# Adafruit_ICM20948.net
KiCad netlist of a schematic drawn in EAGLE
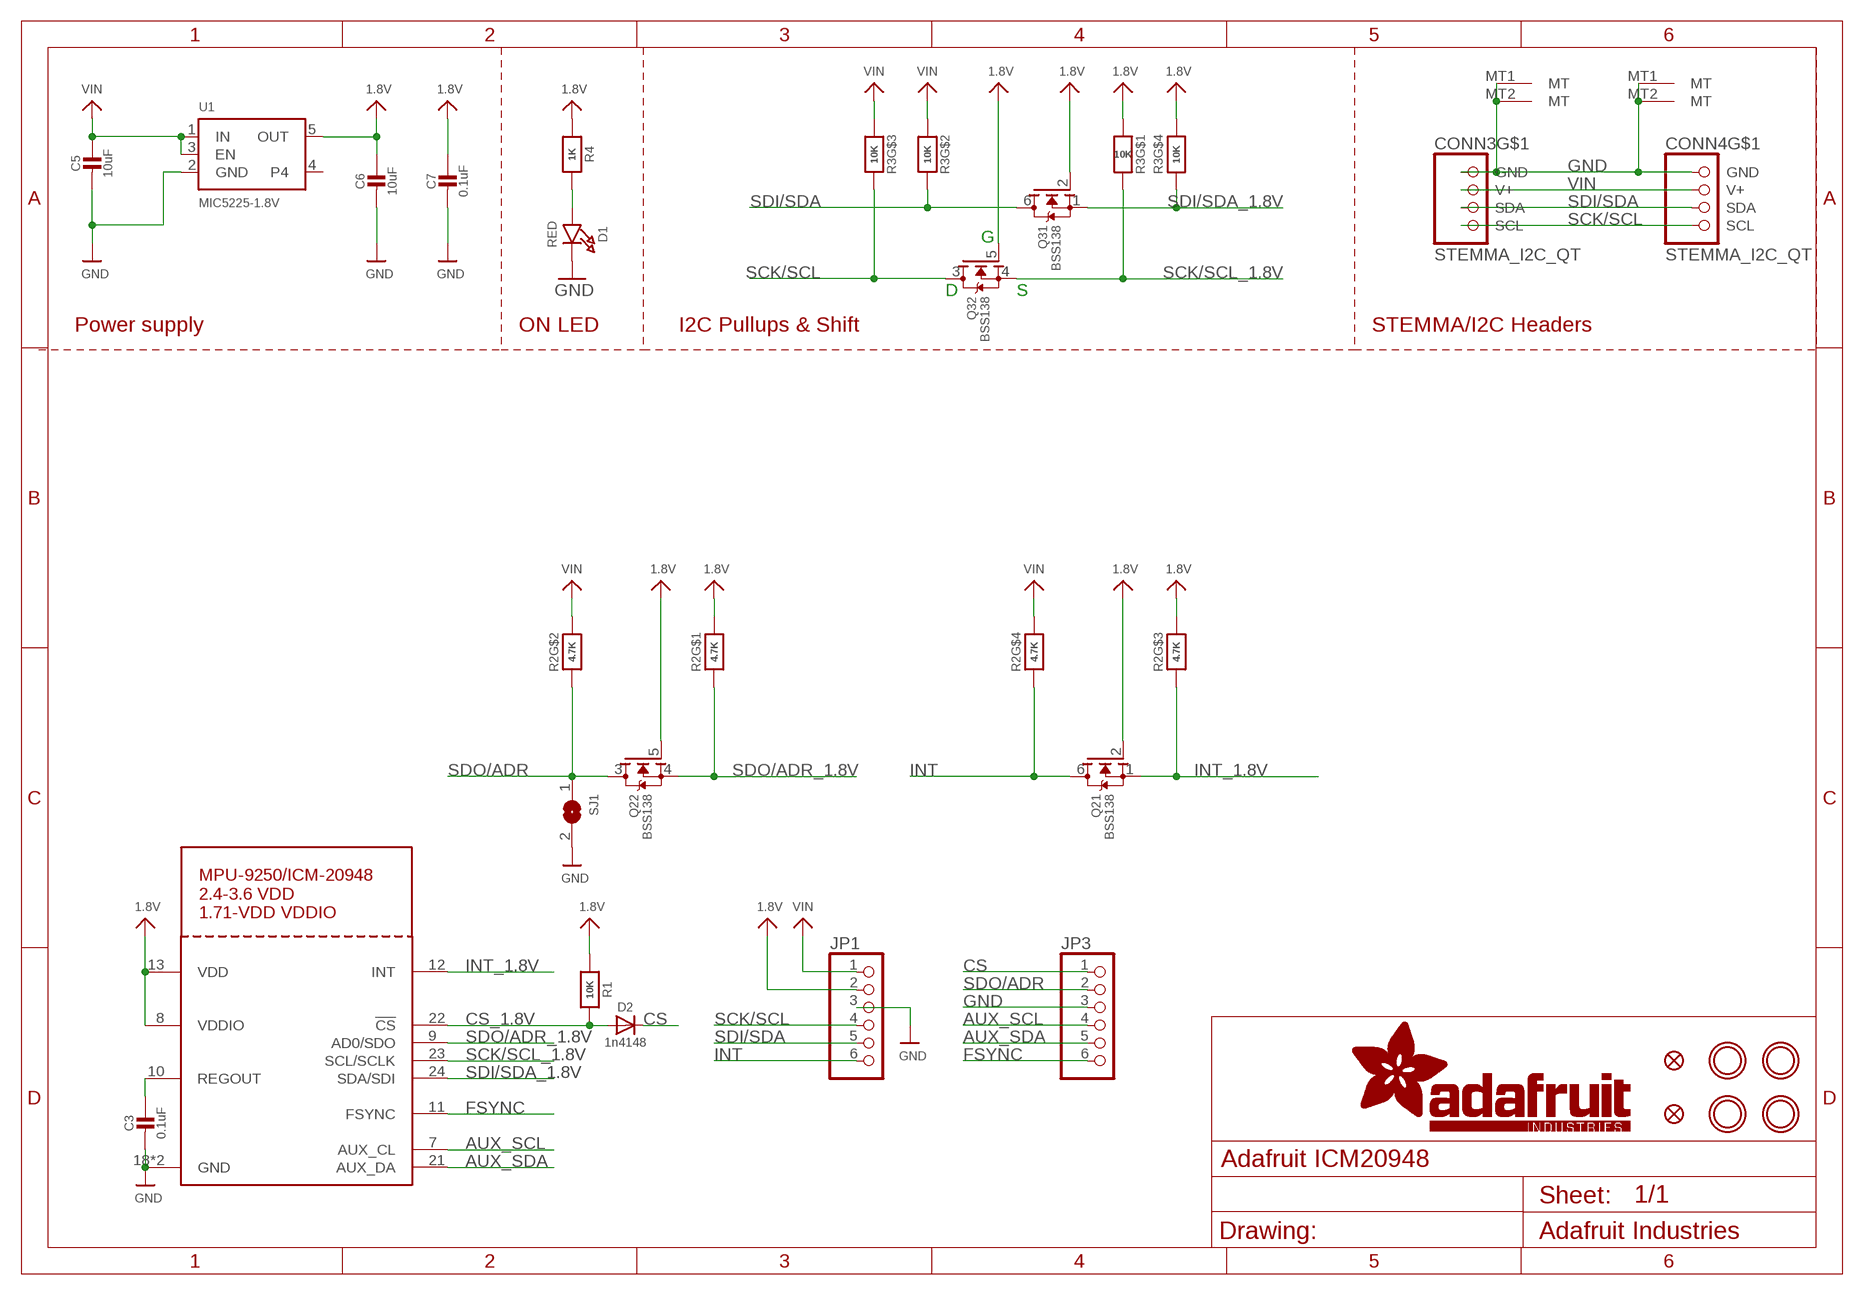
[diagram p0: schematic, sheet 1]

(export (version "E")
  (design (tool "Eeschema 10.0.6"))
  (components
    (comp (ref "C3")
      (value "0.1uF")
      (footprint "eagle-import:0603-NO")
      (libsource (lib "eagle-import") (part "CAP_CERAMIC0603_NO"))
    )
    (comp (ref "C5")
      (value "10uF")
      (footprint "eagle-import:0805-NO")
      (libsource (lib "eagle-import") (part "CAP_CERAMIC0805-NOOUTLINE"))
    )
    (comp (ref "C6")
      (value "10uF")
      (footprint "eagle-import:0805-NO")
      (libsource (lib "eagle-import") (part "CAP_CERAMIC0805-NOOUTLINE"))
    )
    (comp (ref "C7")
      (value "0.1uF")
      (footprint "eagle-import:0603-NO")
      (libsource (lib "eagle-import") (part "CAP_CERAMIC0603_NO"))
    )
    (comp (ref "CONN3")
      (value "STEMMA_I2C_QT")
      (footprint "eagle-import:JST_SH4")
      (libsource (lib "eagle-import") (part "STEMMA_I2C_QT"))
    )
    (comp (ref "CONN4")
      (value "STEMMA_I2C_QT")
      (footprint "eagle-import:JST_SH4")
      (libsource (lib "eagle-import") (part "STEMMA_I2C_QT"))
    )
    (comp (ref "D1")
      (value "RED")
      (footprint "eagle-import:CHIPLED_0603_NOOUTLINE")
      (libsource (lib "eagle-import") (part "LED0603_NOOUTLINE"))
    )
    (comp (ref "D2")
      (value "1n4148")
      (footprint "eagle-import:SOD-323_MINI")
      (libsource (lib "eagle-import") (part "DIODE_SOD323MINI"))
    )
    (comp (ref "FID2")
      (value "FIDUCIAL_1MM")
      (footprint "eagle-import:FIDUCIAL_1MM")
      (libsource (lib "eagle-import") (part "FIDUCIAL_1MM"))
    )
    (comp (ref "FID4")
      (value "FIDUCIAL_1MM")
      (footprint "eagle-import:FIDUCIAL_1MM")
      (libsource (lib "eagle-import") (part "FIDUCIAL_1MM"))
    )
    (comp (ref "JP1")
      (value "HEADER-1X670MIL")
      (footprint "eagle-import:1X06_ROUND_70")
      (libsource (lib "eagle-import") (part "HEADER-1X670MIL"))
    )
    (comp (ref "JP3")
      (value "HEADER-1X670MIL")
      (footprint "eagle-import:1X06_ROUND_70")
      (libsource (lib "eagle-import") (part "HEADER-1X670MIL"))
    )
    (comp (ref "Q2")
      (value "BSS138")
      (footprint "eagle-import:SOT363")
      (libsource (lib "eagle-import") (part "MOSFET-N_DUAL"))
    )
    (comp (ref "Q3")
      (value "BSS138")
      (footprint "eagle-import:SOT363")
      (libsource (lib "eagle-import") (part "MOSFET-N_DUAL"))
    )
    (comp (ref "R1")
      (value "10K")
      (footprint "eagle-import:0603-NO")
      (libsource (lib "eagle-import") (part "RESISTOR_0603_NOOUT"))
    )
    (comp (ref "R2")
      (value "4.7K")
      (footprint "eagle-import:RESPACK_4X0603")
      (libsource (lib "eagle-import") (part "RESISTOR_4PACK"))
    )
    (comp (ref "R3")
      (value "10K")
      (footprint "eagle-import:RESPACK_4X0603")
      (libsource (lib "eagle-import") (part "RESISTOR_4PACK"))
    )
    (comp (ref "R4")
      (value "1K")
      (footprint "eagle-import:0603-NO")
      (libsource (lib "eagle-import") (part "RESISTOR_0603_NOOUT"))
    )
    (comp (ref "SJ1")
      (value "SOLDERJUMPER")
      (footprint "eagle-import:SOLDERJUMPER_ARROW_NOPASTE")
      (libsource (lib "eagle-import") (part "SOLDERJUMPER"))
    )
    (comp (ref "U$21")
      (value "MPU-9250_ICM20948")
      (footprint "eagle-import:QFN24_3MM_NOEP")
      (libsource (lib "eagle-import") (part "MPU-9250_ICM20948"))
    )
    (comp (ref "U$38")
      (value "MOUNTINGHOLE2.5")
      (footprint "eagle-import:MOUNTINGHOLE_2.5_PLATED")
      (libsource (lib "eagle-import") (part "MOUNTINGHOLE2.5"))
    )
    (comp (ref "U$39")
      (value "MOUNTINGHOLE2.5")
      (footprint "eagle-import:MOUNTINGHOLE_2.5_PLATED")
      (libsource (lib "eagle-import") (part "MOUNTINGHOLE2.5"))
    )
    (comp (ref "U$41")
      (value "MOUNTINGHOLE2.5")
      (footprint "eagle-import:MOUNTINGHOLE_2.5_PLATED")
      (libsource (lib "eagle-import") (part "MOUNTINGHOLE2.5"))
    )
    (comp (ref "U$42")
      (value "MOUNTINGHOLE2.5")
      (footprint "eagle-import:MOUNTINGHOLE_2.5_PLATED")
      (libsource (lib "eagle-import") (part "MOUNTINGHOLE2.5"))
    )
    (comp (ref "U1")
      (value "MIC5225-1.8V")
      (footprint "eagle-import:SOT23-5")
      (libsource (lib "eagle-import") (part "VREG_SOT23-5"))
    )
  )
  (nets
    (net (code "1") (name "/AUX_SCL") (class "Default")
      (node (ref "JP3") (pin "4") (pinfunction "4_4") (pintype "passive"))
      (node (ref "U$21") (pin "7") (pinfunction "AUX_CL_7") (pintype "bidirectional"))
    )
    (net (code "2") (name "/AUX_SDA") (class "Default")
      (node (ref "JP3") (pin "5") (pinfunction "5_5") (pintype "passive"))
      (node (ref "U$21") (pin "21") (pinfunction "AUX_DA_21") (pintype "bidirectional"))
    )
    (net (code "3") (name "/CS") (class "Default")
      (node (ref "D2") (pin "C") (pinfunction "C_C") (pintype "passive"))
      (node (ref "JP3") (pin "1") (pinfunction "1_1") (pintype "passive"))
    )
    (net (code "4") (name "/CS_1.8V") (class "Default")
      (node (ref "D2") (pin "A") (pinfunction "A_A") (pintype "passive"))
      (node (ref "R1") (pin "2") (pinfunction "2_2") (pintype "passive"))
      (node (ref "U$21") (pin "22") (pinfunction "~{CS}_22") (pintype "bidirectional"))
    )
    (net (code "5") (name "/FSYNC") (class "Default")
      (node (ref "JP3") (pin "6") (pinfunction "6_6") (pintype "passive"))
      (node (ref "U$21") (pin "11") (pinfunction "FSYNC_11") (pintype "bidirectional"))
    )
    (net (code "6") (name "/INT") (class "Default")
      (node (ref "JP1") (pin "6") (pinfunction "6_6") (pintype "passive"))
      (node (ref "Q2") (pin "6") (pinfunction "D_6") (pintype "bidirectional"))
      (node (ref "R2") (pin "4") (pinfunction "1_4") (pintype "passive"))
    )
    (net (code "7") (name "/INT_1.8V") (class "Default")
      (node (ref "Q2") (pin "1") (pinfunction "S_1") (pintype "bidirectional"))
      (node (ref "R2") (pin "3") (pinfunction "1_3") (pintype "passive"))
      (node (ref "U$21") (pin "12") (pinfunction "INT_12") (pintype "bidirectional"))
    )
    (net (code "8") (name "/SCK{slash}SCL") (class "Default")
      (node (ref "CONN3") (pin "4") (pinfunction "SCL_4") (pintype "passive"))
      (node (ref "CONN4") (pin "4") (pinfunction "SCL_4") (pintype "passive"))
      (node (ref "JP1") (pin "4") (pinfunction "4_4") (pintype "passive"))
      (node (ref "Q3") (pin "3") (pinfunction "D_3") (pintype "bidirectional"))
      (node (ref "R3") (pin "6") (pinfunction "2_6") (pintype "passive"))
    )
    (net (code "9") (name "/SCK{slash}SCL_1.8V") (class "Default")
      (node (ref "Q3") (pin "4") (pinfunction "S_4") (pintype "bidirectional"))
      (node (ref "R3") (pin "1") (pinfunction "1_1") (pintype "passive"))
      (node (ref "U$21") (pin "23") (pinfunction "SCL/SCLK_23") (pintype "bidirectional"))
    )
    (net (code "10") (name "/SDI{slash}SDA") (class "Default")
      (node (ref "CONN3") (pin "3") (pinfunction "SDA_3") (pintype "passive"))
      (node (ref "CONN4") (pin "3") (pinfunction "SDA_3") (pintype "passive"))
      (node (ref "JP1") (pin "5") (pinfunction "5_5") (pintype "passive"))
      (node (ref "Q3") (pin "6") (pinfunction "D_6") (pintype "bidirectional"))
      (node (ref "R3") (pin "7") (pinfunction "2_7") (pintype "passive"))
    )
    (net (code "11") (name "/SDI{slash}SDA_1.8V") (class "Default")
      (node (ref "Q3") (pin "1") (pinfunction "S_1") (pintype "bidirectional"))
      (node (ref "R3") (pin "5") (pinfunction "2_5") (pintype "passive"))
      (node (ref "U$21") (pin "24") (pinfunction "SDA/SDI_24") (pintype "bidirectional"))
    )
    (net (code "12") (name "/SDO{slash}ADR") (class "Default")
      (node (ref "JP3") (pin "2") (pinfunction "2_2") (pintype "passive"))
      (node (ref "Q2") (pin "3") (pinfunction "D_3") (pintype "bidirectional"))
      (node (ref "R2") (pin "2") (pinfunction "1_2") (pintype "passive"))
      (node (ref "SJ1") (pin "1") (pinfunction "1_1") (pintype "passive"))
    )
    (net (code "13") (name "/SDO{slash}ADR_1.8V") (class "Default")
      (node (ref "Q2") (pin "4") (pinfunction "S_4") (pintype "bidirectional"))
      (node (ref "R2") (pin "1") (pinfunction "1_1") (pintype "passive"))
      (node (ref "U$21") (pin "9") (pinfunction "AD0/SDO_9") (pintype "bidirectional"))
    )
    (net (code "14") (name "1.8V") (class "Default")
      (node (ref "C6") (pin "1") (pinfunction "1_1") (pintype "passive"))
      (node (ref "C7") (pin "1") (pinfunction "1_1") (pintype "passive"))
      (node (ref "JP1") (pin "2") (pinfunction "2_2") (pintype "passive"))
      (node (ref "Q2") (pin "2") (pinfunction "G_2") (pintype "bidirectional"))
      (node (ref "Q2") (pin "5") (pinfunction "G_5") (pintype "bidirectional"))
      (node (ref "Q3") (pin "2") (pinfunction "G_2") (pintype "bidirectional"))
      (node (ref "Q3") (pin "5") (pinfunction "G_5") (pintype "bidirectional"))
      (node (ref "R1") (pin "1") (pinfunction "1_1") (pintype "passive"))
      (node (ref "R2") (pin "6") (pinfunction "2_6") (pintype "passive"))
      (node (ref "R2") (pin "8") (pinfunction "2_8") (pintype "passive"))
      (node (ref "R3") (pin "4") (pinfunction "1_4") (pintype "passive"))
      (node (ref "R3") (pin "8") (pinfunction "2_8") (pintype "passive"))
      (node (ref "R4") (pin "1") (pinfunction "1_1") (pintype "passive"))
      (node (ref "U$21") (pin "13") (pinfunction "VDD_13") (pintype "bidirectional"))
      (node (ref "U$21") (pin "8") (pinfunction "VDDIO_8") (pintype "bidirectional"))
      (node (ref "U1") (pin "5") (pinfunction "OUT_5") (pintype "power_in"))
    )
    (net (code "15") (name "GND") (class "Default")
      (node (ref "C3") (pin "2") (pinfunction "2_2") (pintype "passive"))
      (node (ref "C5") (pin "2") (pinfunction "2_2") (pintype "passive"))
      (node (ref "C6") (pin "2") (pinfunction "2_2") (pintype "passive"))
      (node (ref "C7") (pin "2") (pinfunction "2_2") (pintype "passive"))
      (node (ref "CONN3") (pin "1") (pinfunction "GND_1") (pintype "passive"))
      (node (ref "CONN3") (pin "MT1") (pinfunction "MT_MT1") (pintype "bidirectional"))
      (node (ref "CONN3") (pin "MT2") (pinfunction "MT_MT2") (pintype "bidirectional"))
      (node (ref "CONN4") (pin "1") (pinfunction "GND_1") (pintype "passive"))
      (node (ref "CONN4") (pin "MT1") (pinfunction "MT_MT1") (pintype "bidirectional"))
      (node (ref "CONN4") (pin "MT2") (pinfunction "MT_MT2") (pintype "bidirectional"))
      (node (ref "D1") (pin "C") (pinfunction "C_C") (pintype "passive"))
      (node (ref "JP1") (pin "3") (pinfunction "3_3") (pintype "passive"))
      (node (ref "JP3") (pin "3") (pinfunction "3_3") (pintype "passive"))
      (node (ref "SJ1") (pin "2") (pinfunction "2_2") (pintype "passive"))
      (node (ref "U$21") (pin "18") (pinfunction "GND_18") (pintype "bidirectional"))
      (node (ref "U$21") (pin "20") (pinfunction "GND_20") (pintype "bidirectional"))
      (node (ref "U1") (pin "2") (pinfunction "GND_2") (pintype "power_in"))
    )
    (net (code "16") (name "Net-(D1-PadA)") (class "Default")
      (node (ref "D1") (pin "A") (pinfunction "A_A") (pintype "passive"))
      (node (ref "R4") (pin "2") (pinfunction "2_2") (pintype "passive"))
    )
    (net (code "17") (name "Net-(U$21-REGOUT)") (class "Default")
      (node (ref "C3") (pin "1") (pinfunction "1_1") (pintype "passive"))
      (node (ref "U$21") (pin "10") (pinfunction "REGOUT_10") (pintype "bidirectional"))
    )
    (net (code "18") (name "VIN") (class "Default")
      (node (ref "C5") (pin "1") (pinfunction "1_1") (pintype "passive"))
      (node (ref "CONN3") (pin "2") (pinfunction "V+_2") (pintype "passive"))
      (node (ref "CONN4") (pin "2") (pinfunction "V+_2") (pintype "passive"))
      (node (ref "JP1") (pin "1") (pinfunction "1_1") (pintype "passive"))
      (node (ref "R2") (pin "5") (pinfunction "2_5") (pintype "passive"))
      (node (ref "R2") (pin "7") (pinfunction "2_7") (pintype "passive"))
      (node (ref "R3") (pin "2") (pinfunction "1_2") (pintype "passive"))
      (node (ref "R3") (pin "3") (pinfunction "1_3") (pintype "passive"))
      (node (ref "U1") (pin "1") (pinfunction "IN_1") (pintype "power_in"))
      (node (ref "U1") (pin "3") (pinfunction "EN_3") (pintype "input"))
    )
    (net (code "19") (name "unconnected-(U1-P4-Pad4)") (class "Default")
      (node (ref "U1") (pin "4") (pinfunction "P4_4") (pintype "bidirectional"))
    )
  )
)
